# MCU.net
KiCad netlist of a schematic drawn in Altium Designer
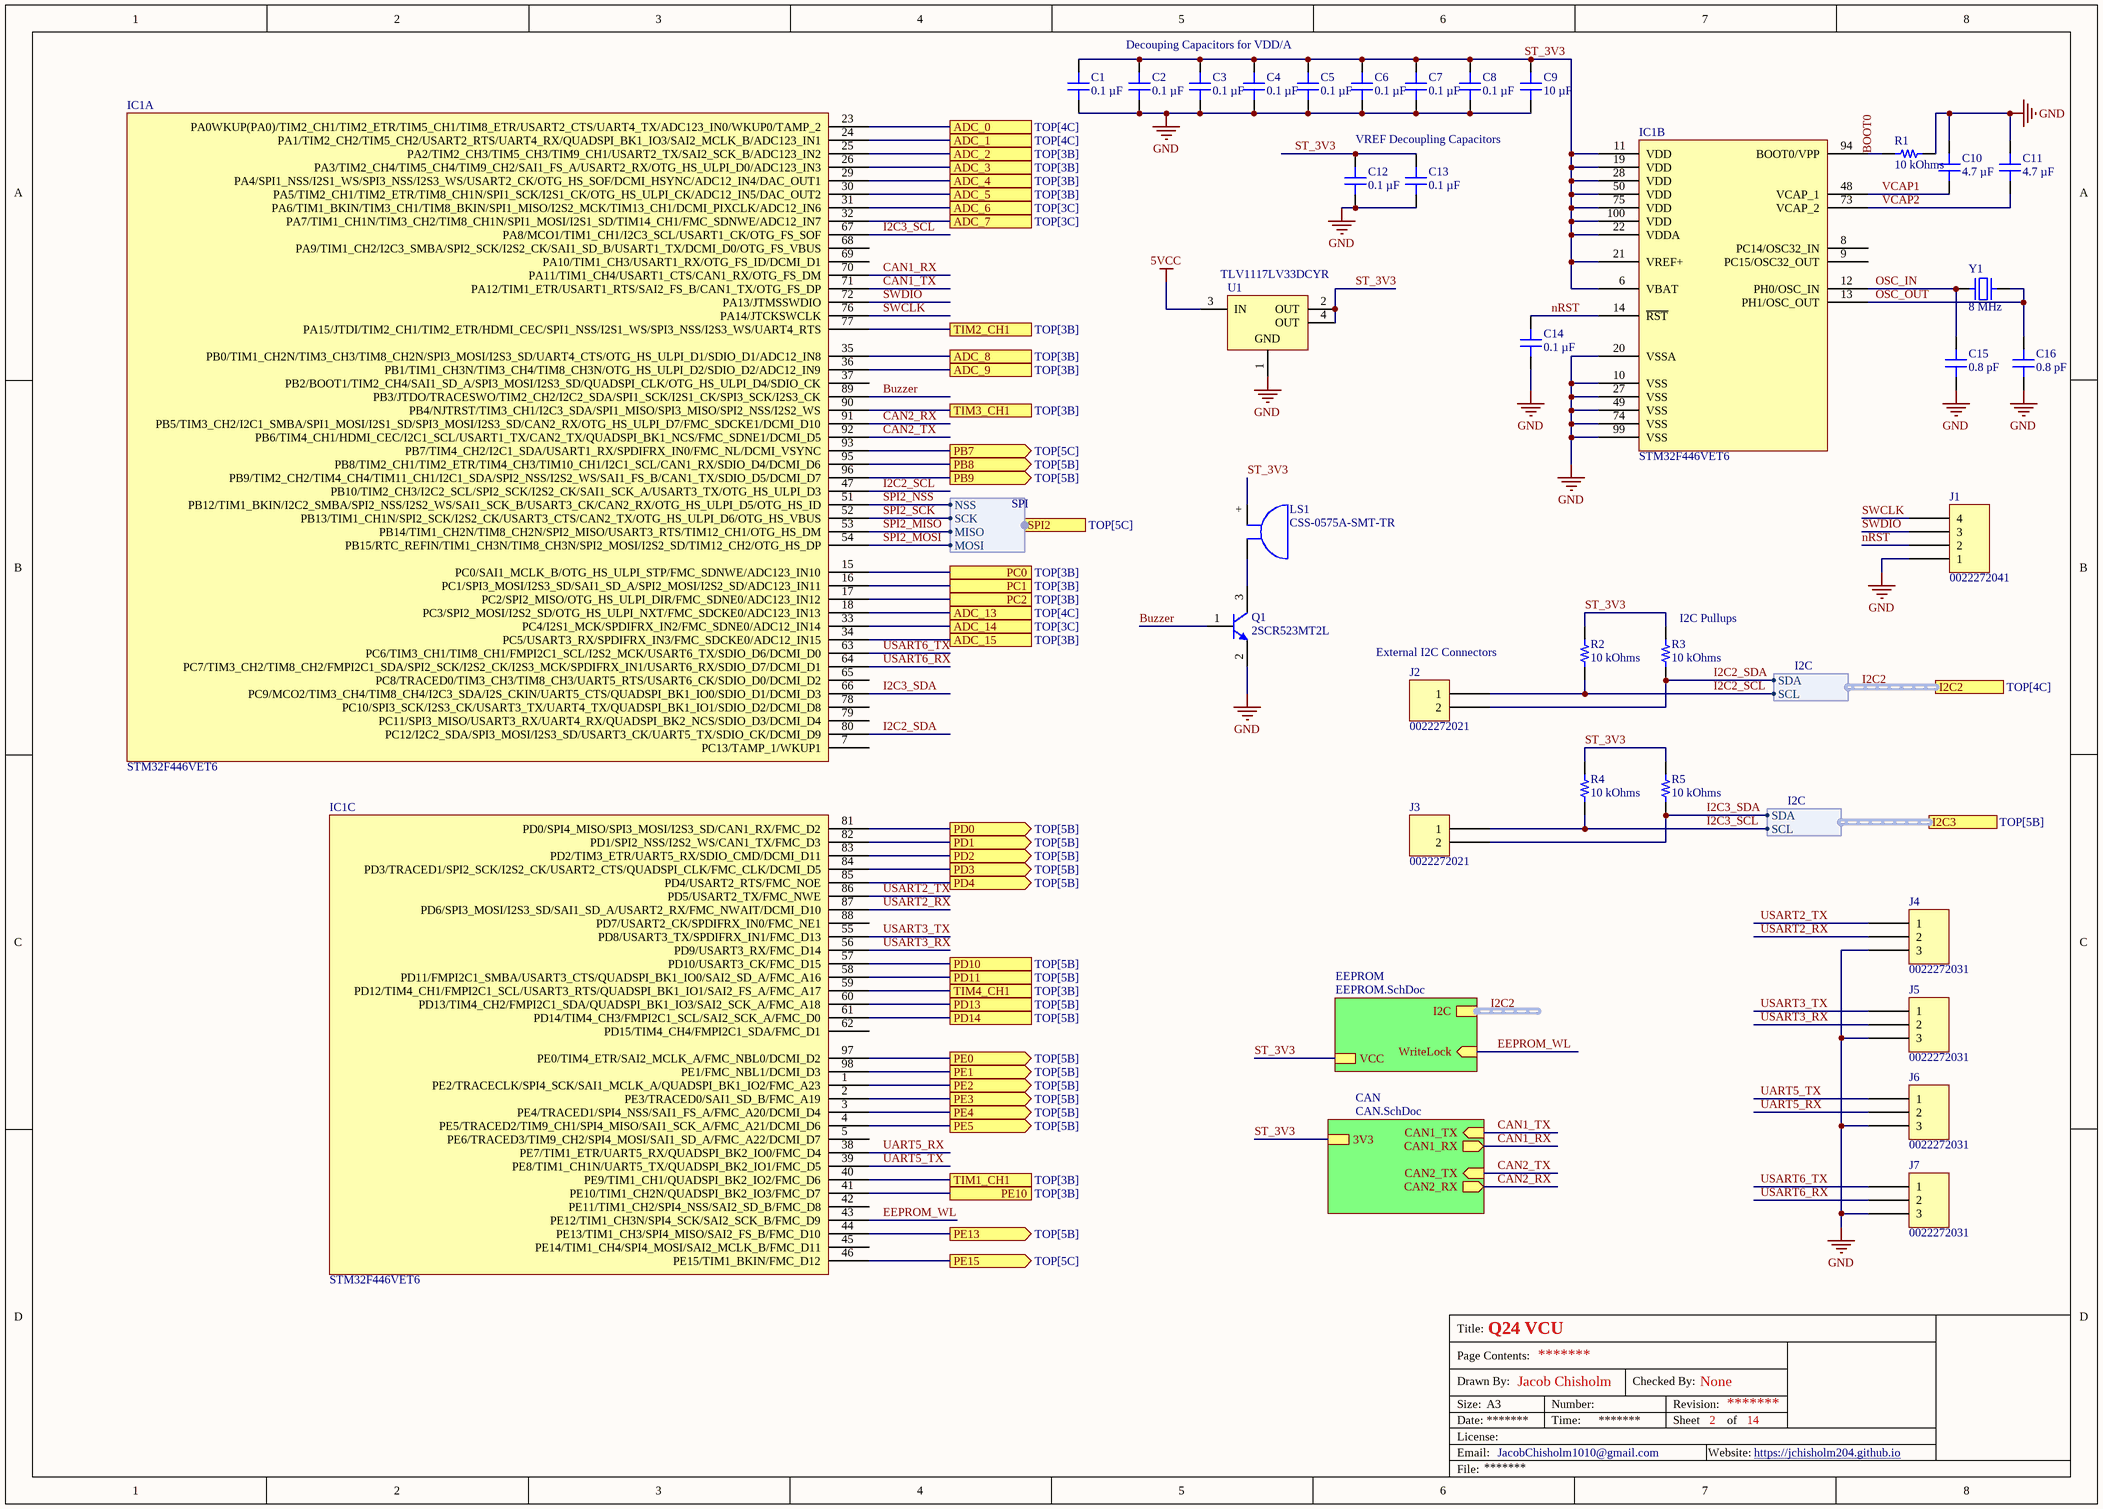
[diagram p0: MCU.SchDoc]

(export (version "E")
  (design (tool "Eeschema 10.0.6"))
  (components
    (comp (ref "C1")
      (value "0.1 µF")
      (footprint "CAP 0603_1608")
      (description "CAP CER 0.1UF 6.3V X7R 0603")
      (fields
        (field (name "PART NUMBER") "6R3X14W104MV4T")
        (field (name "MANUFACTURER") "Johanson Dielectrics Inc.")
      )
      (libsource (lib "altium_library") (part "Capacitor"))
    )
    (comp (ref "C2")
      (value "0.1 µF")
      (footprint "CAP 0603_1608")
      (description "CAP CER 0.1UF 6.3V X7R 0603")
      (fields
        (field (name "PART NUMBER") "6R3X14W104MV4T")
        (field (name "MANUFACTURER") "Johanson Dielectrics Inc.")
      )
      (libsource (lib "altium_library") (part "Capacitor"))
    )
    (comp (ref "C3")
      (value "0.1 µF")
      (footprint "CAP 0603_1608")
      (description "CAP CER 0.1UF 6.3V X7R 0603")
      (fields
        (field (name "PART NUMBER") "6R3X14W104MV4T")
        (field (name "MANUFACTURER") "Johanson Dielectrics Inc.")
      )
      (libsource (lib "altium_library") (part "Capacitor"))
    )
    (comp (ref "C4")
      (value "0.1 µF")
      (footprint "CAP 0603_1608")
      (description "CAP CER 0.1UF 6.3V X7R 0603")
      (fields
        (field (name "PART NUMBER") "6R3X14W104MV4T")
        (field (name "MANUFACTURER") "Johanson Dielectrics Inc.")
      )
      (libsource (lib "altium_library") (part "Capacitor"))
    )
    (comp (ref "C5")
      (value "0.1 µF")
      (footprint "CAP 0603_1608")
      (description "CAP CER 0.1UF 6.3V X7R 0603")
      (fields
        (field (name "PART NUMBER") "6R3X14W104MV4T")
        (field (name "MANUFACTURER") "Johanson Dielectrics Inc.")
      )
      (libsource (lib "altium_library") (part "Capacitor"))
    )
    (comp (ref "C6")
      (value "0.1 µF")
      (footprint "CAP 0603_1608")
      (description "CAP CER 0.1UF 6.3V X7R 0603")
      (fields
        (field (name "PART NUMBER") "6R3X14W104MV4T")
        (field (name "MANUFACTURER") "Johanson Dielectrics Inc.")
      )
      (libsource (lib "altium_library") (part "Capacitor"))
    )
    (comp (ref "C7")
      (value "0.1 µF")
      (footprint "CAP 0603_1608")
      (description "CAP CER 0.1UF 6.3V X7R 0603")
      (fields
        (field (name "PART NUMBER") "6R3X14W104MV4T")
        (field (name "MANUFACTURER") "Johanson Dielectrics Inc.")
      )
      (libsource (lib "altium_library") (part "Capacitor"))
    )
    (comp (ref "C8")
      (value "0.1 µF")
      (footprint "CAP 0603_1608")
      (description "CAP CER 0.1UF 6.3V X7R 0603")
      (fields
        (field (name "PART NUMBER") "6R3X14W104MV4T")
        (field (name "MANUFACTURER") "Johanson Dielectrics Inc.")
      )
      (libsource (lib "altium_library") (part "Capacitor"))
    )
    (comp (ref "C9")
      (value "10 µF")
      (footprint "CAP 0603_1608")
      (description "CAP CER 10UF 35V X5R 0603")
      (fields (field (name "PART NUMBER") "0603DD106MAT2A") (field (name "MANUFACTURER") "KYOCERA AVX"))
      (libsource (lib "altium_library") (part "Capacitor"))
    )
    (comp (ref "C10")
      (value "4.7 µF")
      (footprint "CAP 0603_1608")
      (description "CAP CER 4.7UF 6.3V X5R 0603")
      (fields
        (field (name "PART NUMBER") "0603X475K6R3CT")
        (field (name "MANUFACTURER") "Walsin Technology Corporation")
      )
      (libsource (lib "altium_library") (part "Capacitor"))
    )
    (comp (ref "C11")
      (value "4.7 µF")
      (footprint "CAP 0603_1608")
      (description "CAP CER 4.7UF 6.3V X5R 0603")
      (fields
        (field (name "PART NUMBER") "0603X475K6R3CT")
        (field (name "MANUFACTURER") "Walsin Technology Corporation")
      )
      (libsource (lib "altium_library") (part "Capacitor"))
    )
    (comp (ref "C12")
      (value "0.1 µF")
      (footprint "CAP 0603_1608")
      (description "CAP CER 0.1UF 6.3V X7R 0603")
      (fields
        (field (name "PART NUMBER") "6R3X14W104MV4T")
        (field (name "MANUFACTURER") "Johanson Dielectrics Inc.")
      )
      (libsource (lib "altium_library") (part "Capacitor"))
    )
    (comp (ref "C13")
      (value "0.1 µF")
      (footprint "CAP 0603_1608")
      (description "CAP CER 0.1UF 6.3V X7R 0603")
      (fields
        (field (name "PART NUMBER") "6R3X14W104MV4T")
        (field (name "MANUFACTURER") "Johanson Dielectrics Inc.")
      )
      (libsource (lib "altium_library") (part "Capacitor"))
    )
    (comp (ref "C14")
      (value "0.1 µF")
      (footprint "CAP 0603_1608")
      (description "CAP CER 0.1UF 6.3V X7R 0603")
      (fields
        (field (name "PART NUMBER") "6R3X14W104MV4T")
        (field (name "MANUFACTURER") "Johanson Dielectrics Inc.")
      )
      (libsource (lib "altium_library") (part "Capacitor"))
    )
    (comp (ref "C15")
      (value "0.8 pF")
      (footprint "CAP 0603_1608")
      (description "CAP CER 0.8PF 250V C0G/NP0 0603")
      (fields
        (field (name "PART NUMBER") "251R14S0R8BV4T")
        (field (name "MANUFACTURER") "Johanson Technology Inc.")
      )
      (libsource (lib "altium_library") (part "Capacitor"))
    )
    (comp (ref "C16")
      (value "0.8 pF")
      (footprint "CAP 0603_1608")
      (description "CAP CER 0.8PF 250V C0G/NP0 0603")
      (fields
        (field (name "PART NUMBER") "251R14S0R8BV4T")
        (field (name "MANUFACTURER") "Johanson Technology Inc.")
      )
      (libsource (lib "altium_library") (part "Capacitor"))
    )
    (comp (ref "IC1")
      (value "STM32F446VET6")
      (footprint "ST LQFP-100 14X14MM")
      (description "IC MCU 32BIT 512KB FLASH 100LQFP")
      (fields (field (name "MANUFACTURER") "STMicroelectronics"))
      (libsource (lib "altium_library") (part "ST STM32F446 100PIN"))
    )
    (comp (ref "J1")
      (value "0022272041")
      (footprint "MOLEX KK 0022272041")
      (description "CONN HEADER VERT 4POS 2.54MM")
      (fields (field (name "MANUFACTURER") "Molex"))
      (libsource (lib "altium_library") (part "4 Pin"))
    )
    (comp (ref "J2")
      (value "0022272021")
      (footprint "MOLEX KK 0022272021")
      (description "CONN HEADER VERT 2POS 2.54MM")
      (fields (field (name "MANUFACTURER") "Molex"))
      (libsource (lib "Celestial Altium Library - altium_library") (part "2 Pin"))
    )
    (comp (ref "J3")
      (value "0022272021")
      (footprint "MOLEX KK 0022272021")
      (description "CONN HEADER VERT 2POS 2.54MM")
      (fields (field (name "MANUFACTURER") "Molex"))
      (libsource (lib "Celestial Altium Library - altium_library") (part "2 Pin"))
    )
    (comp (ref "J4")
      (value "0022272031")
      (footprint "MOLEX KK 0022272031")
      (description "CONN HEADER VERT 3POS 2.54MM")
      (libsource (lib "altium_library") (part "3 Pin"))
    )
    (comp (ref "J5")
      (value "0022272031")
      (footprint "MOLEX KK 0022272031")
      (description "CONN HEADER VERT 3POS 2.54MM")
      (libsource (lib "altium_library") (part "3 Pin"))
    )
    (comp (ref "J6")
      (value "0022272031")
      (footprint "MOLEX KK 0022272031")
      (description "CONN HEADER VERT 3POS 2.54MM")
      (libsource (lib "altium_library") (part "3 Pin"))
    )
    (comp (ref "J7")
      (value "0022272031")
      (footprint "MOLEX KK 0022272031")
      (description "CONN HEADER VERT 3POS 2.54MM")
      (libsource (lib "altium_library") (part "3 Pin"))
    )
    (comp (ref "LS1")
      (value "CSS-0575A-SMT-TR")
      (footprint "CUI CSS-0575A-SMT-TR")
      (description "AUDIO MAGNETIC XDCR 2-4V SMD")
      (fields (field (name "MANUFACTURER") "CUI Devices"))
      (libsource (lib "altium_library") (part "Buzzer 2 pin"))
    )
    (comp (ref "Q1")
      (value "2SCR523MT2L")
      (footprint "ROHM SOT-723")
      (description "TRANS NPN 50V 0.1A VMT3")
      (fields (field (name "MANUFACTURER") "Rohm Semiconductor"))
      (libsource (lib "altium_library") (part "ROHM NPN SOT723 BEC"))
    )
    (comp (ref "R1")
      (value "10 kOhms")
      (footprint "RES 0603_1608")
      (description "RES SMD 10K OHM 1% 1/10W 0603")
      (fields (field (name "PART NUMBER") "AA0603FR-0710KL") (field (name "MANUFACTURER") "Yageo"))
      (libsource (lib "altium_library") (part "Resistor"))
    )
    (comp (ref "R2")
      (value "10 kOhms")
      (footprint "RES 0603_1608")
      (description "RES 10K OHM 0.1% 1/5W 0603")
      (fields
        (field (name "PART NUMBER") "RS73F1JTTD1002B")
        (field (name "MANUFACTURER") "KOA Speer Electronics, Inc.")
      )
      (libsource (lib "Celestial Altium Library - altium_library") (part "Resistor"))
    )
    (comp (ref "R3")
      (value "10 kOhms")
      (footprint "RES 0603_1608")
      (description "RES 10K OHM 0.1% 1/5W 0603")
      (fields
        (field (name "PART NUMBER") "RS73F1JTTD1002B")
        (field (name "MANUFACTURER") "KOA Speer Electronics, Inc.")
      )
      (libsource (lib "Celestial Altium Library - altium_library") (part "Resistor"))
    )
    (comp (ref "R4")
      (value "10 kOhms")
      (footprint "RES 0603_1608")
      (description "RES 10K OHM 0.1% 1/5W 0603")
      (fields
        (field (name "PART NUMBER") "RS73F1JTTD1002B")
        (field (name "MANUFACTURER") "KOA Speer Electronics, Inc.")
      )
      (libsource (lib "Celestial Altium Library - altium_library") (part "Resistor"))
    )
    (comp (ref "R5")
      (value "10 kOhms")
      (footprint "RES 0603_1608")
      (description "RES 10K OHM 0.1% 1/5W 0603")
      (fields
        (field (name "PART NUMBER") "RS73F1JTTD1002B")
        (field (name "MANUFACTURER") "KOA Speer Electronics, Inc.")
      )
      (libsource (lib "Celestial Altium Library - altium_library") (part "Resistor"))
    )
    (comp (ref "U1")
      (value "TLV1117LV33DCYR")
      (footprint "DCY0004A_N")
      (fields (field (name "MANUFACTURER") "Texas Instruments"))
      (libsource (lib "Altium Content Vault") (part "TI-TLV1117LV33DCY4"))
    )
    (comp (ref "Y1")
      (value "8 MHz")
      (footprint "NDK NX3225GD")
      (description "CRYSTAL 8.0000MHZ 8PF SMD")
      (fields
        (field (name "PART NUMBER") "NX3225GD-8MHZ-STD-CRA-3")
        (field (name "MANUFACTURER") "NDK America, Inc.")
      )
      (libsource (lib "Celestial Altium Library - altium_library") (part "NDK NX3225GD"))
    )
  )
  (nets
    (net (code "5") (name "/ADC_0") (class "Default")
      (node (ref "IC1") (pin "23") (pinfunction "PA0WKUP(PA0)/TIM2_CH1/TIM2_ETR/TIM5_CH1/TIM8_ETR/USART2_CTS/UART4_TX/ADC123_IN0/WKUP0/TAMP_2_23") (pintype "passive"))
    )
    (net (code "6") (name "/ADC_1") (class "Default")
      (node (ref "IC1") (pin "24") (pinfunction "PA1/TIM2_CH2/TIM5_CH2/USART2_RTS/UART4_RX/QUADSPI_BK1_IO3/SAI2_MCLK_B/ADC123_IN1_24") (pintype "passive"))
    )
    (net (code "7") (name "/ADC_2") (class "Default")
      (node (ref "IC1") (pin "25") (pinfunction "PA2/TIM2_CH3/TIM5_CH3/TIM9_CH1/USART2_TX/SAI2_SCK_B/ADC123_IN2_25") (pintype "passive"))
    )
    (net (code "8") (name "/ADC_3") (class "Default")
      (node (ref "IC1") (pin "26") (pinfunction "PA3/TIM2_CH4/TIM5_CH4/TIM9_CH2/SAI1_FS_A/USART2_RX/OTG_HS_ULPI_D0/ADC123_IN3_26") (pintype "passive"))
    )
    (net (code "9") (name "/ADC_4") (class "Default")
      (node (ref "IC1") (pin "29") (pinfunction "PA4/SPI1_NSS/I2S1_WS/SPI3_NSS/I2S3_WS/USART2_CK/OTG_HS_SOF/DCMI_HSYNC/ADC12_IN4/DAC_OUT1_29") (pintype "passive"))
    )
    (net (code "10") (name "/ADC_5") (class "Default")
      (node (ref "IC1") (pin "30") (pinfunction "PA5/TIM2_CH1/TIM2_ETR/TIM8_CH1N/SPI1_SCK/I2S1_CK/OTG_HS_ULPI_CK/ADC12_IN5/DAC_OUT2_30") (pintype "passive"))
    )
    (net (code "11") (name "/ADC_6") (class "Default")
      (node (ref "IC1") (pin "31") (pinfunction "PA6/TIM1_BKIN/TIM3_CH1/TIM8_BKIN/SPI1_MISO/I2S2_MCK/TIM13_CH1/DCMI_PIXCLK/ADC12_IN6_31") (pintype "passive"))
    )
    (net (code "12") (name "/ADC_7") (class "Default")
      (node (ref "IC1") (pin "32") (pinfunction "PA7/TIM1_CH1N/TIM3_CH2/TIM8_CH1N/SPI1_MOSI/I2S1_SD/TIM14_CH1/FMC_SDNWE/ADC12_IN7_32") (pintype "passive"))
    )
    (net (code "13") (name "/ADC_8") (class "Default")
      (node (ref "IC1") (pin "35") (pinfunction "PB0/TIM1_CH2N/TIM3_CH3/TIM8_CH2N/SPI3_MOSI/I2S3_SD/UART4_CTS/OTG_HS_ULPI_D1/SDIO_D1/ADC12_IN8_35") (pintype "passive"))
    )
    (net (code "14") (name "/ADC_9") (class "Default")
      (node (ref "IC1") (pin "36") (pinfunction "PB1/TIM1_CH3N/TIM3_CH4/TIM8_CH3N/OTG_HS_ULPI_D2/SDIO_D2/ADC12_IN9_36") (pintype "passive"))
    )
    (net (code "15") (name "/ADC_13") (class "Default")
      (node (ref "IC1") (pin "18") (pinfunction "PC3/SPI2_MOSI/I2S2_SD/OTG_HS_ULPI_NXT/FMC_SDCKE0/ADC123_IN13_18") (pintype "passive"))
    )
    (net (code "16") (name "/ADC_14") (class "Default")
      (node (ref "IC1") (pin "33") (pinfunction "PC4/I2S1_MCK/SPDIFRX_IN2/FMC_SDNE0/ADC12_IN14_33") (pintype "passive"))
    )
    (net (code "17") (name "/ADC_15") (class "Default")
      (node (ref "IC1") (pin "34") (pinfunction "PC5/USART3_RX/SPDIFRX_IN3/FMC_SDCKE0/ADC12_IN15_34") (pintype "passive"))
    )
    (net (code "18") (name "/BOOT0") (class "Default")
      (node (ref "IC1") (pin "94") (pinfunction "BOOT0/VPP_94") (pintype "passive"))
      (node (ref "R1") (pin "1") (pinfunction "1_1") (pintype "passive"))
    )
    (net (code "19") (name "/Buzzer") (class "Default")
      (node (ref "IC1") (pin "89") (pinfunction "PB3/JTDO/TRACESWO/TIM2_CH2/I2C2_SDA/SPI1_SCK/I2S1_CK/SPI3_SCK/I2S3_CK_89") (pintype "passive"))
      (node (ref "Q1") (pin "1") (pinfunction "B_1") (pintype "passive"))
    )
    (net (code "20") (name "/CAN1_RX") (class "Default")
      (node (ref "IC1") (pin "70") (pinfunction "PA11/TIM1_CH4/USART1_CTS/CAN1_RX/OTG_FS_DM_70") (pintype "passive"))
    )
    (net (code "21") (name "/CAN1_TX") (class "Default")
      (node (ref "IC1") (pin "71") (pinfunction "PA12/TIM1_ETR/USART1_RTS/SAI2_FS_B/CAN1_TX/OTG_FS_DP_71") (pintype "passive"))
    )
    (net (code "22") (name "/CAN2_RX") (class "Default")
      (node (ref "IC1") (pin "91") (pinfunction "PB5/TIM3_CH2/I2C1_SMBA/SPI1_MOSI/I2S1_SD/SPI3_MOSI/I2S3_SD/CAN2_RX/OTG_HS_ULPI_D7/FMC_SDCKE1/DCMI_D10_91") (pintype "passive"))
    )
    (net (code "23") (name "/CAN2_TX") (class "Default")
      (node (ref "IC1") (pin "92") (pinfunction "PB6/TIM4_CH1/HDMI_CEC/I2C1_SCL/USART1_TX/CAN2_TX/QUADSPI_BK1_NCS/FMC_SDNE1/DCMI_D5_92") (pintype "passive"))
    )
    (net (code "24") (name "/EEPROM_WL") (class "Default")
      (node (ref "IC1") (pin "43") (pinfunction "PE12/TIM1_CH3N/SPI4_SCK/SAI2_SCK_B/FMC_D9_43") (pintype "passive"))
    )
    (net (code "25") (name "/I2C2_SCL") (class "Default")
      (node (ref "IC1") (pin "47") (pinfunction "PB10/TIM2_CH3/I2C2_SCL/SPI2_SCK/I2S2_CK/SAI1_SCK_A/USART3_TX/OTG_HS_ULPI_D3_47") (pintype "passive"))
      (node (ref "J2") (pin "1") (pinfunction "1_1") (pintype "passive"))
      (node (ref "R2") (pin "1") (pinfunction "1_1") (pintype "passive"))
    )
    (net (code "26") (name "/I2C2_SDA") (class "Default")
      (node (ref "IC1") (pin "80") (pinfunction "PC12/I2C2_SDA/SPI3_MOSI/I2S3_SD/USART3_CK/UART5_TX/SDIO_CK/DCMI_D9_80") (pintype "passive"))
      (node (ref "J2") (pin "2") (pinfunction "2_2") (pintype "passive"))
      (node (ref "R3") (pin "1") (pinfunction "1_1") (pintype "passive"))
    )
    (net (code "28") (name "/I2C3_SCL") (class "Default")
      (node (ref "IC1") (pin "67") (pinfunction "PA8/MCO1/TIM1_CH1/I2C3_SCL/USART1_CK/OTG_FS_SOF_67") (pintype "passive"))
      (node (ref "J3") (pin "1") (pinfunction "1_1") (pintype "passive"))
      (node (ref "R4") (pin "1") (pinfunction "1_1") (pintype "passive"))
    )
    (net (code "29") (name "/I2C3_SDA") (class "Default")
      (node (ref "IC1") (pin "66") (pinfunction "PC9/MCO2/TIM3_CH4/TIM8_CH4/I2C3_SDA/I2S_CKIN/UART5_CTS/QUADSPI_BK1_IO0/SDIO_D1/DCMI_D3_66") (pintype "passive"))
      (node (ref "J3") (pin "2") (pinfunction "2_2") (pintype "passive"))
      (node (ref "R5") (pin "1") (pinfunction "1_1") (pintype "passive"))
    )
    (net (code "30") (name "/OSC_IN") (class "Default")
      (node (ref "C15") (pin "2") (pinfunction "2_2") (pintype "passive"))
      (node (ref "IC1") (pin "12") (pinfunction "PH0/OSC_IN_12") (pintype "passive"))
      (node (ref "Y1") (pin "1") (pinfunction "1_1") (pintype "passive"))
    )
    (net (code "31") (name "/OSC_OUT") (class "Default")
      (node (ref "C16") (pin "2") (pinfunction "2_2") (pintype "passive"))
      (node (ref "IC1") (pin "13") (pinfunction "PH1/OSC_OUT_13") (pintype "passive"))
      (node (ref "Y1") (pin "2") (pinfunction "2_2") (pintype "passive"))
    )
    (net (code "32") (name "/PB7") (class "Default")
      (node (ref "IC1") (pin "93") (pinfunction "PB7/TIM4_CH2/I2C1_SDA/USART1_RX/SPDIFRX_IN0/FMC_NL/DCMI_VSYNC_93") (pintype "passive"))
    )
    (net (code "33") (name "/PB8") (class "Default")
      (node (ref "IC1") (pin "95") (pinfunction "PB8/TIM2_CH1/TIM2_ETR/TIM4_CH3/TIM10_CH1/I2C1_SCL/CAN1_RX/SDIO_D4/DCMI_D6_95") (pintype "passive"))
    )
    (net (code "34") (name "/PB9") (class "Default")
      (node (ref "IC1") (pin "96") (pinfunction "PB9/TIM2_CH2/TIM4_CH4/TIM11_CH1/I2C1_SDA/SPI2_NSS/I2S2_WS/SAI1_FS_B/CAN1_TX/SDIO_D5/DCMI_D7_96") (pintype "passive"))
    )
    (net (code "35") (name "/PC0") (class "Default")
      (node (ref "IC1") (pin "15") (pinfunction "PC0/SAI1_MCLK_B/OTG_HS_ULPI_STP/FMC_SDNWE/ADC123_IN10_15") (pintype "passive"))
    )
    (net (code "36") (name "/PC1") (class "Default")
      (node (ref "IC1") (pin "16") (pinfunction "PC1/SPI3_MOSI/I2S3_SD/SAI1_SD_A/SPI2_MOSI/I2S2_SD/ADC123_IN11_16") (pintype "passive"))
    )
    (net (code "37") (name "/PC2") (class "Default")
      (node (ref "IC1") (pin "17") (pinfunction "PC2/SPI2_MISO/OTG_HS_ULPI_DIR/FMC_SDNE0/ADC123_IN12_17") (pintype "passive"))
    )
    (net (code "38") (name "/PD0") (class "Default")
      (node (ref "IC1") (pin "81") (pinfunction "PD0/SPI4_MISO/SPI3_MOSI/I2S3_SD/CAN1_RX/FMC_D2_81") (pintype "passive"))
    )
    (net (code "39") (name "/PD1") (class "Default")
      (node (ref "IC1") (pin "82") (pinfunction "PD1/SPI2_NSS/I2S2_WS/CAN1_TX/FMC_D3_82") (pintype "passive"))
    )
    (net (code "40") (name "/PD2") (class "Default")
      (node (ref "IC1") (pin "83") (pinfunction "PD2/TIM3_ETR/UART5_RX/SDIO_CMD/DCMI_D11_83") (pintype "passive"))
    )
    (net (code "41") (name "/PD3") (class "Default")
      (node (ref "IC1") (pin "84") (pinfunction "PD3/TRACED1/SPI2_SCK/I2S2_CK/USART2_CTS/QUADSPI_CLK/FMC_CLK/DCMI_D5_84") (pintype "passive"))
    )
    (net (code "42") (name "/PD4") (class "Default")
      (node (ref "IC1") (pin "85") (pinfunction "PD4/USART2_RTS/FMC_NOE_85") (pintype "passive"))
    )
    (net (code "43") (name "/PD10") (class "Default")
      (node (ref "IC1") (pin "57") (pinfunction "PD10/USART3_CK/FMC_D15_57") (pintype "passive"))
    )
    (net (code "44") (name "/PD11") (class "Default")
      (node (ref "IC1") (pin "58") (pinfunction "PD11/FMPI2C1_SMBA/USART3_CTS/QUADSPI_BK1_IO0/SAI2_SD_A/FMC_A16_58") (pintype "passive"))
    )
    (net (code "45") (name "/PD13") (class "Default")
      (node (ref "IC1") (pin "60") (pinfunction "PD13/TIM4_CH2/FMPI2C1_SDA/QUADSPI_BK1_IO3/SAI2_SCK_A/FMC_A18_60") (pintype "passive"))
    )
    (net (code "46") (name "/PD14") (class "Default")
      (node (ref "IC1") (pin "61") (pinfunction "PD14/TIM4_CH3/FMPI2C1_SCL/SAI2_SCK_A/FMC_D0_61") (pintype "passive"))
    )
    (net (code "47") (name "/PE0") (class "Default")
      (node (ref "IC1") (pin "97") (pinfunction "PE0/TIM4_ETR/SAI2_MCLK_A/FMC_NBL0/DCMI_D2_97") (pintype "passive"))
    )
    (net (code "48") (name "/PE1") (class "Default")
      (node (ref "IC1") (pin "98") (pinfunction "PE1/FMC_NBL1/DCMI_D3_98") (pintype "passive"))
    )
    (net (code "49") (name "/PE2") (class "Default")
      (node (ref "IC1") (pin "1") (pinfunction "PE2/TRACECLK/SPI4_SCK/SAI1_MCLK_A/QUADSPI_BK1_IO2/FMC_A23_1") (pintype "passive"))
    )
    (net (code "50") (name "/PE3") (class "Default")
      (node (ref "IC1") (pin "2") (pinfunction "PE3/TRACED0/SAI1_SD_B/FMC_A19_2") (pintype "passive"))
    )
    (net (code "51") (name "/PE4") (class "Default")
      (node (ref "IC1") (pin "3") (pinfunction "PE4/TRACED1/SPI4_NSS/SAI1_FS_A/FMC_A20/DCMI_D4_3") (pintype "passive"))
    )
    (net (code "52") (name "/PE5") (class "Default")
      (node (ref "IC1") (pin "4") (pinfunction "PE5/TRACED2/TIM9_CH1/SPI4_MISO/SAI1_SCK_A/FMC_A21/DCMI_D6_4") (pintype "passive"))
    )
    (net (code "53") (name "/PE10") (class "Default")
      (node (ref "IC1") (pin "41") (pinfunction "PE10/TIM1_CH2N/QUADSPI_BK2_IO3/FMC_D7_41") (pintype "passive"))
    )
    (net (code "54") (name "/PE13") (class "Default")
      (node (ref "IC1") (pin "44") (pinfunction "PE13/TIM1_CH3/SPI4_MISO/SAI2_FS_B/FMC_D10_44") (pintype "passive"))
    )
    (net (code "55") (name "/PE15") (class "Default")
      (node (ref "IC1") (pin "46") (pinfunction "PE15/TIM1_BKIN/FMC_D12_46") (pintype "passive"))
    )
    (net (code "56") (name "/SPI2_MISO") (class "Default")
      (node (ref "IC1") (pin "53") (pinfunction "PB14/TIM1_CH2N/TIM8_CH2N/SPI2_MISO/USART3_RTS/TIM12_CH1/OTG_HS_DM_53") (pintype "passive"))
    )
    (net (code "57") (name "/SPI2_MOSI") (class "Default")
      (node (ref "IC1") (pin "54") (pinfunction "PB15/RTC_REFIN/TIM1_CH3N/TIM8_CH3N/SPI2_MOSI/I2S2_SD/TIM12_CH2/OTG_HS_DP_54") (pintype "passive"))
    )
    (net (code "58") (name "/SPI2_NSS") (class "Default")
      (node (ref "IC1") (pin "51") (pinfunction "PB12/TIM1_BKIN/I2C2_SMBA/SPI2_NSS/I2S2_WS/SAI1_SCK_B/USART3_CK/CAN2_RX/OTG_HS_ULPI_D5/OTG_HS_ID_51") (pintype "passive"))
    )
    (net (code "59") (name "/SPI2_SCK") (class "Default")
      (node (ref "IC1") (pin "52") (pinfunction "PB13/TIM1_CH1N/SPI2_SCK/I2S2_CK/USART3_CTS/CAN2_TX/OTG_HS_ULPI_D6/OTG_HS_VBUS_52") (pintype "passive"))
    )
    (net (code "60") (name "/ST_3V3") (class "Default")
      (node (ref "C1") (pin "2") (pinfunction "2_2") (pintype "passive"))
      (node (ref "C12") (pin "2") (pinfunction "2_2") (pintype "passive"))
      (node (ref "C13") (pin "2") (pinfunction "2_2") (pintype "passive"))
      (node (ref "C2") (pin "2") (pinfunction "2_2") (pintype "passive"))
      (node (ref "C3") (pin "2") (pinfunction "2_2") (pintype "passive"))
      (node (ref "C4") (pin "2") (pinfunction "2_2") (pintype "passive"))
      (node (ref "C5") (pin "2") (pinfunction "2_2") (pintype "passive"))
      (node (ref "C6") (pin "2") (pinfunction "2_2") (pintype "passive"))
      (node (ref "C7") (pin "2") (pinfunction "2_2") (pintype "passive"))
      (node (ref "C8") (pin "2") (pinfunction "2_2") (pintype "passive"))
      (node (ref "C9") (pin "2") (pinfunction "2_2") (pintype "passive"))
      (node (ref "IC1") (pin "100") (pinfunction "VDD_100") (pintype "passive"))
      (node (ref "IC1") (pin "11") (pinfunction "VDD_11") (pintype "passive"))
      (node (ref "IC1") (pin "19") (pinfunction "VDD_19") (pintype "passive"))
      (node (ref "IC1") (pin "21") (pinfunction "VREF+_21") (pintype "passive"))
      (node (ref "IC1") (pin "22") (pinfunction "VDDA_22") (pintype "passive"))
      (node (ref "IC1") (pin "28") (pinfunction "VDD_28") (pintype "passive"))
      (node (ref "IC1") (pin "50") (pinfunction "VDD_50") (pintype "passive"))
      (node (ref "IC1") (pin "6") (pinfunction "VBAT_6") (pintype "passive"))
      (node (ref "IC1") (pin "75") (pinfunction "VDD_75") (pintype "passive"))
      (node (ref "LS1") (pin "+") (pinfunction "+_+") (pintype "passive"))
      (node (ref "R2") (pin "2") (pinfunction "2_2") (pintype "passive"))
      (node (ref "R3") (pin "2") (pinfunction "2_2") (pintype "passive"))
      (node (ref "R4") (pin "2") (pinfunction "2_2") (pintype "passive"))
      (node (ref "R5") (pin "2") (pinfunction "2_2") (pintype "passive"))
      (node (ref "U1") (pin "2") (pinfunction "OUT_2") (pintype "power_in"))
      (node (ref "U1") (pin "4") (pinfunction "OUT_4") (pintype "power_in"))
    )
    (net (code "61") (name "/SWCLK") (class "Default")
      (node (ref "IC1") (pin "76") (pinfunction "PA14/JTCKSWCLK_76") (pintype "passive"))
      (node (ref "J1") (pin "4") (pinfunction "4_4") (pintype "passive"))
    )
    (net (code "62") (name "/SWDIO") (class "Default")
      (node (ref "IC1") (pin "72") (pinfunction "PA13/JTMSSWDIO_72") (pintype "passive"))
      (node (ref "J1") (pin "3") (pinfunction "3_3") (pintype "passive"))
    )
    (net (code "63") (name "/TIM1_CH1") (class "Default")
      (node (ref "IC1") (pin "40") (pinfunction "PE9/TIM1_CH1/QUADSPI_BK2_IO2/FMC_D6_40") (pintype "passive"))
    )
    (net (code "64") (name "/TIM2_CH1") (class "Default")
      (node (ref "IC1") (pin "77") (pinfunction "PA15/JTDI/TIM2_CH1/TIM2_ETR/HDMI_CEC/SPI1_NSS/I2S1_WS/SPI3_NSS/I2S3_WS/UART4_RTS_77") (pintype "passive"))
    )
    (net (code "65") (name "/TIM3_CH1") (class "Default")
      (node (ref "IC1") (pin "90") (pinfunction "PB4/NJTRST/TIM3_CH1/I2C3_SDA/SPI1_MISO/SPI3_MISO/SPI2_NSS/I2S2_WS_90") (pintype "passive"))
    )
    (net (code "66") (name "/TIM4_CH1") (class "Default")
      (node (ref "IC1") (pin "59") (pinfunction "PD12/TIM4_CH1/FMPI2C1_SCL/USART3_RTS/QUADSPI_BK1_IO1/SAI2_FS_A/FMC_A17_59") (pintype "passive"))
    )
    (net (code "67") (name "/UART5_RX") (class "Default")
      (node (ref "IC1") (pin "38") (pinfunction "PE7/TIM1_ETR/UART5_RX/QUADSPI_BK2_IO0/FMC_D4_38") (pintype "passive"))
      (node (ref "J6") (pin "2") (pinfunction "2_2") (pintype "passive"))
    )
    (net (code "68") (name "/UART5_TX") (class "Default")
      (node (ref "IC1") (pin "39") (pinfunction "PE8/TIM1_CH1N/UART5_TX/QUADSPI_BK2_IO1/FMC_D5_39") (pintype "passive"))
      (node (ref "J6") (pin "1") (pinfunction "1_1") (pintype "passive"))
    )
    (net (code "69") (name "/USART2_RX") (class "Default")
      (node (ref "IC1") (pin "87") (pinfunction "PD6/SPI3_MOSI/I2S3_SD/SAI1_SD_A/USART2_RX/FMC_NWAIT/DCMI_D10_87") (pintype "passive"))
      (node (ref "J4") (pin "2") (pinfunction "2_2") (pintype "passive"))
    )
    (net (code "70") (name "/USART2_TX") (class "Default")
      (node (ref "IC1") (pin "86") (pinfunction "PD5/USART2_TX/FMC_NWE_86") (pintype "passive"))
      (node (ref "J4") (pin "1") (pinfunction "1_1") (pintype "passive"))
    )
    (net (code "71") (name "/USART3_RX") (class "Default")
      (node (ref "IC1") (pin "56") (pinfunction "PD9/USART3_RX/FMC_D14_56") (pintype "passive"))
      (node (ref "J5") (pin "2") (pinfunction "2_2") (pintype "passive"))
    )
    (net (code "72") (name "/USART3_TX") (class "Default")
      (node (ref "IC1") (pin "55") (pinfunction "PD8/USART3_TX/SPDIFRX_IN1/FMC_D13_55") (pintype "passive"))
      (node (ref "J5") (pin "1") (pinfunction "1_1") (pintype "passive"))
    )
    (net (code "73") (name "/USART6_RX") (class "Default")
      (node (ref "IC1") (pin "64") (pinfunction "PC7/TIM3_CH2/TIM8_CH2/FMPI2C1_SDA/SPI2_SCK/I2S2_CK/I2S3_MCK/SPDIFRX_IN1/USART6_RX/SDIO_D7/DCMI_D1_64") (pintype "passive"))
      (node (ref "J7") (pin "2") (pinfunction "2_2") (pintype "passive"))
    )
    (net (code "74") (name "/USART6_TX") (class "Default")
      (node (ref "IC1") (pin "63") (pinfunction "PC6/TIM3_CH1/TIM8_CH1/FMPI2C1_SCL/I2S2_MCK/USART6_TX/SDIO_D6/DCMI_D0_63") (pintype "passive"))
      (node (ref "J7") (pin "1") (pinfunction "1_1") (pintype "passive"))
    )
    (net (code "75") (name "/VCAP1") (class "Default")
      (node (ref "C10") (pin "1") (pinfunction "1_1") (pintype "passive"))
      (node (ref "IC1") (pin "48") (pinfunction "VCAP_1_48") (pintype "passive"))
    )
    (net (code "76") (name "/VCAP2") (class "Default")
      (node (ref "C11") (pin "1") (pinfunction "1_1") (pintype "passive"))
      (node (ref "IC1") (pin "73") (pinfunction "VCAP_2_73") (pintype "passive"))
    )
    (net (code "77") (name "/nRST") (class "Default")
      (node (ref "C14") (pin "2") (pinfunction "2_2") (pintype "passive"))
      (node (ref "IC1") (pin "14") (pinfunction "~{RST}_14") (pintype "passive"))
      (node (ref "J1") (pin "2") (pinfunction "2_2") (pintype "passive"))
    )
    (net (code "81") (name "5VCC") (class "Default")
      (node (ref "U1") (pin "3") (pinfunction "IN_3") (pintype "power_in"))
    )
    (net (code "82") (name "GND") (class "Default")
      (node (ref "C1") (pin "1") (pinfunction "1_1") (pintype "passive"))
      (node (ref "C10") (pin "2") (pinfunction "2_2") (pintype "passive"))
      (node (ref "C11") (pin "2") (pinfunction "2_2") (pintype "passive"))
      (node (ref "C12") (pin "1") (pinfunction "1_1") (pintype "passive"))
      (node (ref "C13") (pin "1") (pinfunction "1_1") (pintype "passive"))
      (node (ref "C14") (pin "1") (pinfunction "1_1") (pintype "passive"))
      (node (ref "C15") (pin "1") (pinfunction "1_1") (pintype "passive"))
      (node (ref "C16") (pin "1") (pinfunction "1_1") (pintype "passive"))
      (node (ref "C2") (pin "1") (pinfunction "1_1") (pintype "passive"))
      (node (ref "C3") (pin "1") (pinfunction "1_1") (pintype "passive"))
      (node (ref "C4") (pin "1") (pinfunction "1_1") (pintype "passive"))
      (node (ref "C5") (pin "1") (pinfunction "1_1") (pintype "passive"))
      (node (ref "C6") (pin "1") (pinfunction "1_1") (pintype "passive"))
      (node (ref "C7") (pin "1") (pinfunction "1_1") (pintype "passive"))
      (node (ref "C8") (pin "1") (pinfunction "1_1") (pintype "passive"))
      (node (ref "C9") (pin "1") (pinfunction "1_1") (pintype "passive"))
      (node (ref "IC1") (pin "10") (pinfunction "VSS_10") (pintype "passive"))
      (node (ref "IC1") (pin "20") (pinfunction "VSSA_20") (pintype "passive"))
      (node (ref "IC1") (pin "27") (pinfunction "VSS_27") (pintype "passive"))
      (node (ref "IC1") (pin "49") (pinfunction "VSS_49") (pintype "passive"))
      (node (ref "IC1") (pin "74") (pinfunction "VSS_74") (pintype "passive"))
      (node (ref "IC1") (pin "99") (pinfunction "VSS_99") (pintype "passive"))
      (node (ref "J1") (pin "1") (pinfunction "1_1") (pintype "passive"))
      (node (ref "J4") (pin "3") (pinfunction "3_3") (pintype "passive"))
      (node (ref "J5") (pin "3") (pinfunction "3_3") (pintype "passive"))
      (node (ref "J6") (pin "3") (pinfunction "3_3") (pintype "passive"))
      (node (ref "J7") (pin "3") (pinfunction "3_3") (pintype "passive"))
      (node (ref "Q1") (pin "2") (pinfunction "E_2") (pintype "passive"))
      (node (ref "R1") (pin "2") (pinfunction "2_2") (pintype "passive"))
      (node (ref "U1") (pin "1") (pinfunction "GND_1") (pintype "power_in"))
    )
    (net (code "83") (name "Net-(Q1-C)") (class "Default")
      (node (ref "LS1") (pin "-") (pinfunction "-_-") (pintype "passive"))
      (node (ref "Q1") (pin "3") (pinfunction "C_3") (pintype "passive"))
    )
    (net (code "84") (name "unconnected-(IC1A-PA9{slash}TIM1_CH2{slash}I2C3_SMBA{slash}SPI2_SCK{slash}I2S2_CK{slash}SAI1_SD_B{slash}USART1_TX{slash}DCMI_D0{slash}OTG_FS_VBUS-Pad68)") (class "Default")
      (node (ref "IC1") (pin "68") (pinfunction "PA9/TIM1_CH2/I2C3_SMBA/SPI2_SCK/I2S2_CK/SAI1_SD_B/USART1_TX/DCMI_D0/OTG_FS_VBUS_68") (pintype "passive"))
    )
    (net (code "85") (name "unconnected-(IC1A-PA10{slash}TIM1_CH3{slash}USART1_RX{slash}OTG_FS_ID{slash}DCMI_D1-Pad69)") (class "Default")
      (node (ref "IC1") (pin "69") (pinfunction "PA10/TIM1_CH3/USART1_RX/OTG_FS_ID/DCMI_D1_69") (pintype "passive"))
    )
    (net (code "86") (name "unconnected-(IC1A-PB2{slash}BOOT1{slash}TIM2_CH4{slash}SAI1_SD_A{slash}SPI3_MOSI{slash}I2S3_SD{slash}QUADSPI_CLK{slash}OTG_HS_ULPI_D4{slash}SDIO_CK-Pad37)") (class "Default")
      (node (ref "IC1") (pin "37") (pinfunction "PB2/BOOT1/TIM2_CH4/SAI1_SD_A/SPI3_MOSI/I2S3_SD/QUADSPI_CLK/OTG_HS_ULPI_D4/SDIO_CK_37") (pintype "passive"))
    )
    (net (code "87") (name "unconnected-(IC1A-PC8{slash}TRACED0{slash}TIM3_CH3{slash}TIM8_CH3{slash}UART5_RTS{slash}USART6_CK{slash}SDIO_D0{slash}DCMI_D2-Pad65)") (class "Default")
      (node (ref "IC1") (pin "65") (pinfunction "PC8/TRACED0/TIM3_CH3/TIM8_CH3/UART5_RTS/USART6_CK/SDIO_D0/DCMI_D2_65") (pintype "passive"))
    )
    (net (code "88") (name "unconnected-(IC1A-PC10{slash}SPI3_SCK{slash}I2S3_CK{slash}USART3_TX{slash}UART4_TX{slash}QUADSPI_BK1_IO1{slash}SDIO_D2{slash}DCMI_D8-Pad78)") (class "Default")
      (node (ref "IC1") (pin "78") (pinfunction "PC10/SPI3_SCK/I2S3_CK/USART3_TX/UART4_TX/QUADSPI_BK1_IO1/SDIO_D2/DCMI_D8_78") (pintype "passive"))
    )
    (net (code "89") (name "unconnected-(IC1A-PC11{slash}SPI3_MISO{slash}USART3_RX{slash}UART4_RX{slash}QUADSPI_BK2_NCS{slash}SDIO_D3{slash}DCMI_D4-Pad79)") (class "Default")
      (node (ref "IC1") (pin "79") (pinfunction "PC11/SPI3_MISO/USART3_RX/UART4_RX/QUADSPI_BK2_NCS/SDIO_D3/DCMI_D4_79") (pintype "passive"))
    )
    (net (code "90") (name "unconnected-(IC1A-PC13{slash}TAMP_1{slash}WKUP1-Pad7)") (class "Default")
      (node (ref "IC1") (pin "7") (pinfunction "PC13/TAMP_1/WKUP1_7") (pintype "passive"))
    )
    (net (code "91") (name "unconnected-(IC1B-PC14{slash}OSC32_IN-Pad8)") (class "Default")
      (node (ref "IC1") (pin "8") (pinfunction "PC14/OSC32_IN_8") (pintype "passive"))
    )
    (net (code "92") (name "unconnected-(IC1B-PC15{slash}OSC32_OUT-Pad9)") (class "Default")
      (node (ref "IC1") (pin "9") (pinfunction "PC15/OSC32_OUT_9") (pintype "passive"))
    )
    (net (code "93") (name "unconnected-(IC1C-PD7{slash}USART2_CK{slash}SPDIFRX_IN0{slash}FMC_NE1-Pad88)") (class "Default")
      (node (ref "IC1") (pin "88") (pinfunction "PD7/USART2_CK/SPDIFRX_IN0/FMC_NE1_88") (pintype "passive"))
    )
    (net (code "94") (name "unconnected-(IC1C-PD15{slash}TIM4_CH4{slash}FMPI2C1_SDA{slash}FMC_D1-Pad62)") (class "Default")
      (node (ref "IC1") (pin "62") (pinfunction "PD15/TIM4_CH4/FMPI2C1_SDA/FMC_D1_62") (pintype "passive"))
    )
    (net (code "95") (name "unconnected-(IC1C-PE6{slash}TRACED3{slash}TIM9_CH2{slash}SPI4_MOSI{slash}SAI1_SD_A{slash}FMC_A22{slash}DCMI_D7-Pad5)") (class "Default")
      (node (ref "IC1") (pin "5") (pinfunction "PE6/TRACED3/TIM9_CH2/SPI4_MOSI/SAI1_SD_A/FMC_A22/DCMI_D7_5") (pintype "passive"))
    )
    (net (code "96") (name "unconnected-(IC1C-PE11{slash}TIM1_CH2{slash}SPI4_NSS{slash}SAI2_SD_B{slash}FMC_D8-Pad42)") (class "Default")
      (node (ref "IC1") (pin "42") (pinfunction "PE11/TIM1_CH2/SPI4_NSS/SAI2_SD_B/FMC_D8_42") (pintype "passive"))
    )
    (net (code "97") (name "unconnected-(IC1C-PE14{slash}TIM1_CH4{slash}SPI4_MOSI{slash}SAI2_MCLK_B{slash}FMC_D11-Pad45)") (class "Default")
      (node (ref "IC1") (pin "45") (pinfunction "PE14/TIM1_CH4/SPI4_MOSI/SAI2_MCLK_B/FMC_D11_45") (pintype "passive"))
    )
  )
)
